# MOD_SONIDO.net
KiCad netlist of a schematic drawn in Altium Designer
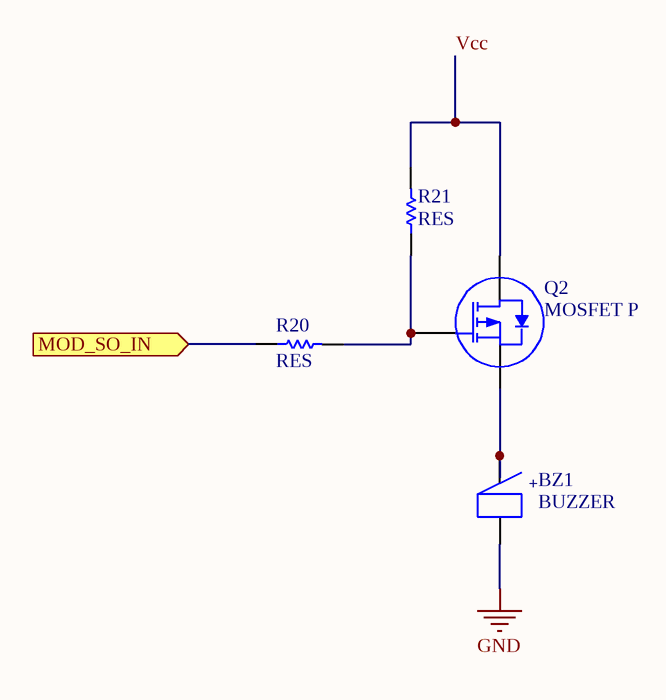
[diagram p0: MOD_SONIDO.SchDoc]

(export (version "E")
  (design (tool "Eeschema 10.0.6"))
  (components
    (comp (ref "BZ1") (value "BUZZER") (footprint "BUZZER 12MM") (libsource (lib "LIBEBAL") (part "BUZZER")))
    (comp (ref "Q2") (value "MOSFET P") (footprint "SOT23") (libsource (lib "LIBEBAL") (part "MOSFET P")))
    (comp (ref "R20") (value "RES") (footprint "0805") (libsource (lib "LIBEBAL") (part "RES")))
    (comp (ref "R21") (value "RES") (footprint "0805") (libsource (lib "LIBEBAL") (part "RES")))
  )
  (nets
    (net (code "1") (name "/MOD_SO_IN") (class "Default")
      (node (ref "R20") (pin "1") (pinfunction "1_1") (pintype "passive"))
    )
    (net (code "2") (name "/Vcc") (class "Default")
      (node (ref "Q2") (pin "2") (pinfunction "D_2") (pintype "passive"))
      (node (ref "R21") (pin "2") (pinfunction "2_2") (pintype "passive"))
    )
    (net (code "3") (name "GND") (class "Default")
      (node (ref "BZ1") (pin "2") (pinfunction "2_2") (pintype "passive"))
    )
    (net (code "4") (name "Net-(Q2-G)") (class "Default")
      (node (ref "Q2") (pin "1") (pinfunction "G_1") (pintype "passive"))
      (node (ref "R20") (pin "2") (pinfunction "2_2") (pintype "passive"))
      (node (ref "R21") (pin "1") (pinfunction "1_1") (pintype "passive"))
    )
    (net (code "5") (name "Net-(Q2-S)") (class "Default")
      (node (ref "BZ1") (pin "1") (pinfunction "1_1") (pintype "passive"))
      (node (ref "Q2") (pin "3") (pinfunction "S_3") (pintype "passive"))
    )
  )
)
